# Z7_FUNCTION3.net
KiCad netlist of a schematic drawn in Altium Designer
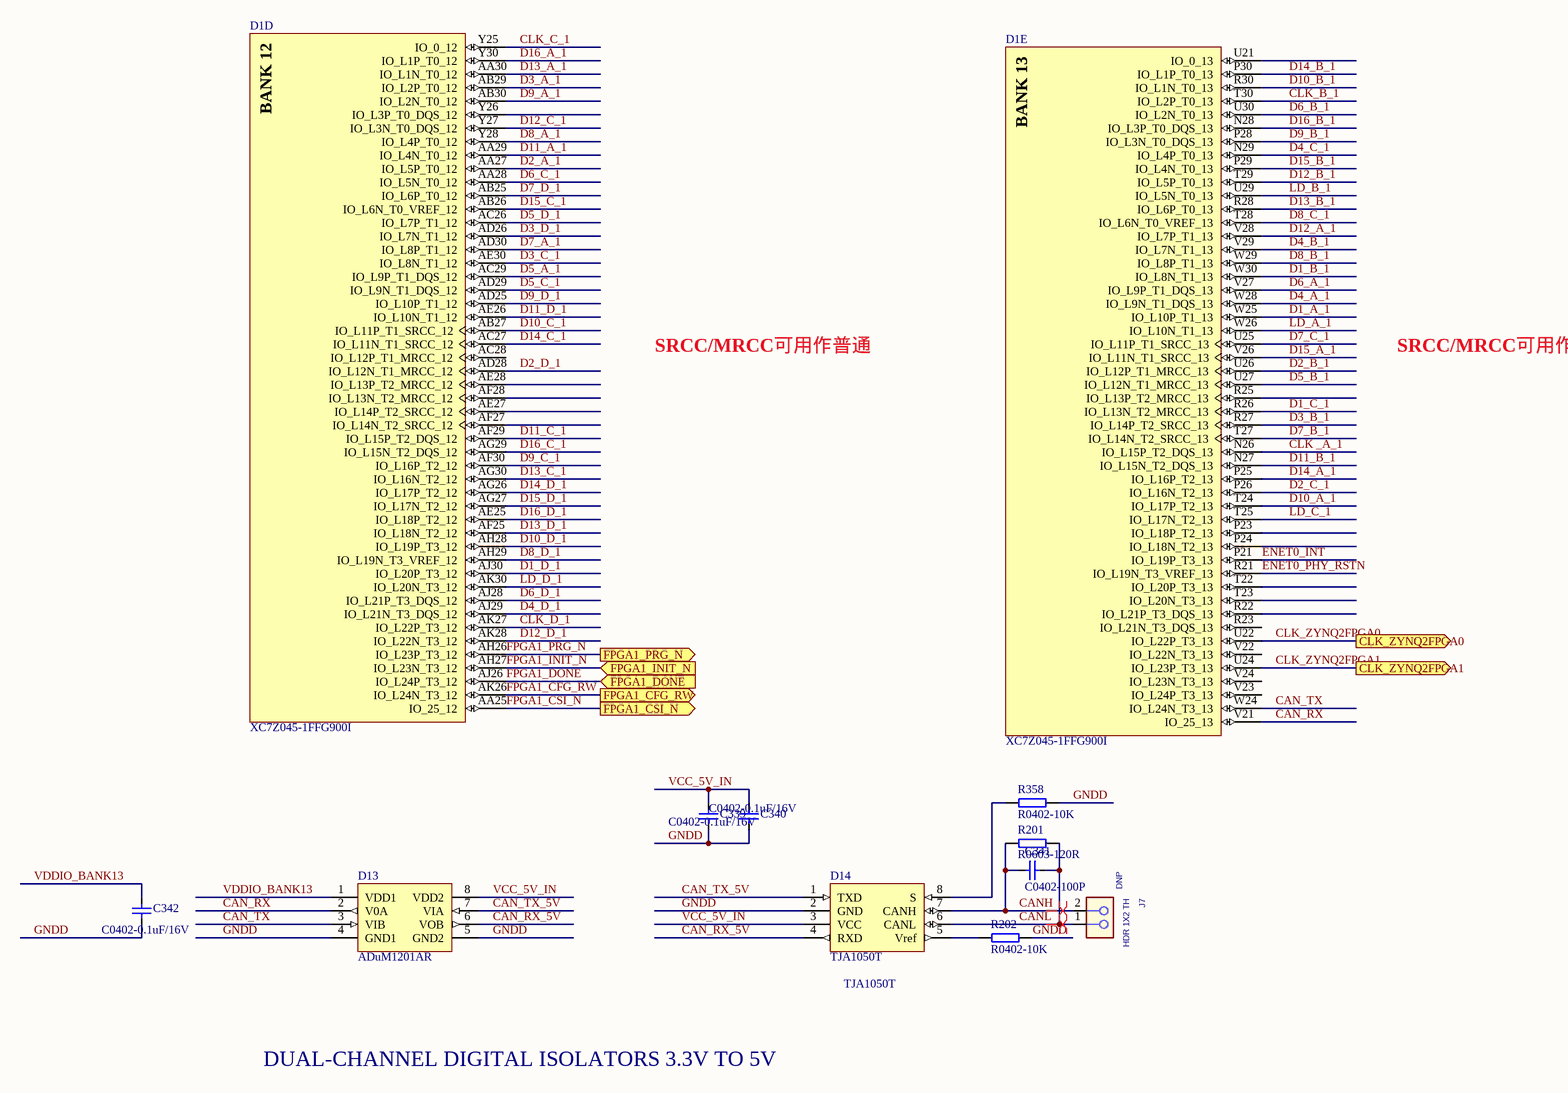
[diagram p0: Z7_FUNCTION3.SchDoc]

(export (version "E")
  (design (tool "Eeschema 10.0.6"))
  (components
    (comp (ref "C339")
      (value "C0402-0.1uF/16V")
      (footprint "C0402")
      (description "X7R")
      (fields (field (name "SCHEMATIC_PART") "CAP") (field (name "MANUFACTURER") "SAMSUNG"))
      (libsource (lib "Database_Libs1") (part "CAP"))
    )
    (comp (ref "C340")
      (value "C0402-0.1uF/16V")
      (footprint "C0402")
      (description "X7R")
      (fields (field (name "SCHEMATIC_PART") "CAP") (field (name "MANUFACTURER") "SAMSUNG"))
      (libsource (lib "Database_Libs1") (part "CAP"))
    )
    (comp (ref "C341")
      (value "C0402-100P")
      (footprint "C0402")
      (description "X7R")
      (fields (field (name "SCHEMATIC_PART") "CAP") (field (name "MANUFACTURER") "SAMSUNG"))
      (libsource (lib "Database_Libs1") (part "CAP"))
    )
    (comp (ref "C342")
      (value "C0402-0.1uF/16V")
      (footprint "C0402")
      (description "X7R")
      (fields (field (name "SCHEMATIC_PART") "CAP") (field (name "MANUFACTURER") "SAMSUNG"))
      (libsource (lib "Database_Libs1") (part "CAP"))
    )
    (comp (ref "D1")
      (value "XC7Z045-1FFG900I")
      (footprint "FFG900")
      (fields (field (name "GENERIC PART NUMBER") "XC7Z045") (field (name "MANUFACTURER") "Xilinx"))
      (libsource (lib "Xilinx Zynq-7000") (part "XC7Z045-1FFG900I"))
    )
    (comp (ref "D13")
      (value "ADuM1201AR")
      (footprint "SOIC-8")
      (description "Quad-Channel Digital Isolators")
      (libsource (lib "Database_Libs1") (part "ADuM1201AR"))
    )
    (comp (ref "D14")
      (value "TJA1050T")
      (footprint "SOIC-8")
      (description "以太网芯片，high speed CAN transceiver,3.3V,SO-8PIN")
      (fields
        (field (name "PART_NUMBER") "TJA1050T")
        (field (name "SCHEMATIC_PART") "TJA1050")
        (field (name "MANUFACTURER") "PHILIPS")
      )
      (libsource (lib "Database_Libs1") (part "TJA1050"))
    )
    (comp (ref "J7")
      (value "HDR 1X2 TH")
      (description "HDR 1X2 TH 100MIL SP 339H AU 98L")
      (fields (field (name "ASSY_OPT") "DNP"))
      (libsource (lib "*") (part "CONN_HDR_2X1"))
    )
    (comp (ref "R201")
      (value "R0603-120R")
      (footprint "R0603")
      (fields (field (name "SCHEMATIC_PART") "RES") (field (name "MANUFACTURER") "YAGEO"))
      (libsource (lib "Database_Libs1") (part "RES"))
    )
    (comp (ref "R202")
      (value "R0402-10K")
      (footprint "R0402")
      (fields (field (name "SCHEMATIC_PART") "RES") (field (name "MANUFACTURER") "SAMSUNG"))
      (libsource (lib "Database_Libs1") (part "RES"))
    )
    (comp (ref "R358")
      (value "R0402-10K")
      (footprint "R0402")
      (fields (field (name "SCHEMATIC_PART") "RES") (field (name "MANUFACTURER") "SAMSUNG"))
      (libsource (lib "Database_Libs1") (part "RES"))
    )
  )
  (nets
    (net (code "1") (name "/CANH") (class "Default")
      (node (ref "C341") (pin "1") (pinfunction "1_1") (pintype "passive"))
      (node (ref "D14") (pin "7") (pinfunction "CANH_7") (pintype "bidirectional"))
      (node (ref "J7") (pin "2") (pinfunction "2_2") (pintype "passive"))
      (node (ref "R201") (pin "2") (pintype "passive"))
    )
    (net (code "2") (name "/CANL") (class "Default")
      (node (ref "C341") (pin "2") (pinfunction "2_2") (pintype "passive"))
      (node (ref "D14") (pin "6") (pinfunction "CANL_6") (pintype "bidirectional"))
      (node (ref "J7") (pin "1") (pinfunction "1_1") (pintype "passive"))
      (node (ref "R201") (pin "1") (pintype "passive"))
    )
    (net (code "3") (name "/CAN_RX") (class "Default")
      (node (ref "D1") (pin "V21") (pinfunction "IO_25_13_V21") (pintype "bidirectional"))
      (node (ref "D13") (pin "2") (pinfunction "V0A_2") (pintype "output"))
    )
    (net (code "4") (name "/CAN_RX_5V") (class "Default")
      (node (ref "D13") (pin "6") (pinfunction "VOB_6") (pintype "output"))
      (node (ref "D14") (pin "4") (pinfunction "RXD_4") (pintype "output"))
    )
    (net (code "5") (name "/CAN_TX") (class "Default")
      (node (ref "D1") (pin "W24") (pinfunction "IO_L24N_T3_13_W24") (pintype "bidirectional"))
      (node (ref "D13") (pin "3") (pinfunction "VIB_3") (pintype "input"))
    )
    (net (code "6") (name "/CAN_TX_5V") (class "Default")
      (node (ref "D13") (pin "7") (pinfunction "VIA_7") (pintype "input"))
      (node (ref "D14") (pin "1") (pinfunction "TXD_1") (pintype "input"))
    )
    (net (code "7") (name "/CLK _A_1") (class "Default")
      (node (ref "D1") (pin "N26") (pinfunction "IO_L15P_T2_DQS_13_N26") (pintype "bidirectional"))
    )
    (net (code "8") (name "/CLK_B_1") (class "Default")
      (node (ref "D1") (pin "T30") (pinfunction "IO_L2P_T0_13_T30") (pintype "bidirectional"))
    )
    (net (code "9") (name "/CLK_C_1") (class "Default")
      (node (ref "D1") (pin "Y25") (pinfunction "IO_0_12_Y25") (pintype "bidirectional"))
    )
    (net (code "10") (name "/CLK_D_1") (class "Default")
      (node (ref "D1") (pin "AK27") (pinfunction "IO_L22P_T3_12_AK27") (pintype "bidirectional"))
    )
    (net (code "11") (name "/CLK_ZYNQ2FPGA0") (class "Default")
      (node (ref "D1") (pin "U22") (pinfunction "IO_L22P_T3_13_U22") (pintype "bidirectional"))
    )
    (net (code "12") (name "/CLK_ZYNQ2FPGA1") (class "Default")
      (node (ref "D1") (pin "U24") (pinfunction "IO_L23P_T3_13_U24") (pintype "bidirectional"))
    )
    (net (code "13") (name "/D1_A_1") (class "Default")
      (node (ref "D1") (pin "W25") (pinfunction "IO_L10P_T1_13_W25") (pintype "bidirectional"))
    )
    (net (code "14") (name "/D1_B_1") (class "Default")
      (node (ref "D1") (pin "W30") (pinfunction "IO_L8N_T1_13_W30") (pintype "bidirectional"))
    )
    (net (code "15") (name "/D1_C_1") (class "Default")
      (node (ref "D1") (pin "R26") (pinfunction "IO_L13N_T2_MRCC_13_R26") (pintype "bidirectional"))
    )
    (net (code "16") (name "/D1_D_1") (class "Default")
      (node (ref "D1") (pin "AJ30") (pinfunction "IO_L20P_T3_12_AJ30") (pintype "bidirectional"))
    )
    (net (code "17") (name "/D2_A_1") (class "Default")
      (node (ref "D1") (pin "AA27") (pinfunction "IO_L5P_T0_12_AA27") (pintype "bidirectional"))
    )
    (net (code "18") (name "/D2_B_1") (class "Default")
      (node (ref "D1") (pin "U26") (pinfunction "IO_L12P_T1_MRCC_13_U26") (pintype "bidirectional"))
    )
    (net (code "19") (name "/D2_C_1") (class "Default")
      (node (ref "D1") (pin "P26") (pinfunction "IO_L16N_T2_13_P26") (pintype "bidirectional"))
    )
    (net (code "20") (name "/D2_D_1") (class "Default")
      (node (ref "D1") (pin "AD28") (pinfunction "IO_L12N_T1_MRCC_12_AD28") (pintype "bidirectional"))
    )
    (net (code "21") (name "/D3_A_1") (class "Default")
      (node (ref "D1") (pin "AB29") (pinfunction "IO_L2P_T0_12_AB29") (pintype "bidirectional"))
    )
    (net (code "22") (name "/D3_B_1") (class "Default")
      (node (ref "D1") (pin "R27") (pinfunction "IO_L14P_T2_SRCC_13_R27") (pintype "bidirectional"))
    )
    (net (code "23") (name "/D3_C_1") (class "Default")
      (node (ref "D1") (pin "AE30") (pinfunction "IO_L8N_T1_12_AE30") (pintype "bidirectional"))
    )
    (net (code "24") (name "/D3_D_1") (class "Default")
      (node (ref "D1") (pin "AD26") (pinfunction "IO_L7N_T1_12_AD26") (pintype "bidirectional"))
    )
    (net (code "25") (name "/D4_A_1") (class "Default")
      (node (ref "D1") (pin "W28") (pinfunction "IO_L9N_T1_DQS_13_W28") (pintype "bidirectional"))
    )
    (net (code "26") (name "/D4_B_1") (class "Default")
      (node (ref "D1") (pin "V29") (pinfunction "IO_L7N_T1_13_V29") (pintype "bidirectional"))
    )
    (net (code "27") (name "/D4_C_1") (class "Default")
      (node (ref "D1") (pin "N29") (pinfunction "IO_L4P_T0_13_N29") (pintype "bidirectional"))
    )
    (net (code "28") (name "/D4_D_1") (class "Default")
      (node (ref "D1") (pin "AJ29") (pinfunction "IO_L21N_T3_DQS_12_AJ29") (pintype "bidirectional"))
    )
    (net (code "29") (name "/D5_A_1") (class "Default")
      (node (ref "D1") (pin "AC29") (pinfunction "IO_L9P_T1_DQS_12_AC29") (pintype "bidirectional"))
    )
    (net (code "30") (name "/D5_B_1") (class "Default")
      (node (ref "D1") (pin "U27") (pinfunction "IO_L12N_T1_MRCC_13_U27") (pintype "bidirectional"))
    )
    (net (code "31") (name "/D5_C_1") (class "Default")
      (node (ref "D1") (pin "AD29") (pinfunction "IO_L9N_T1_DQS_12_AD29") (pintype "bidirectional"))
    )
    (net (code "32") (name "/D5_D_1") (class "Default")
      (node (ref "D1") (pin "AC26") (pinfunction "IO_L7P_T1_12_AC26") (pintype "bidirectional"))
    )
    (net (code "33") (name "/D6_A_1") (class "Default")
      (node (ref "D1") (pin "V27") (pinfunction "IO_L9P_T1_DQS_13_V27") (pintype "bidirectional"))
    )
    (net (code "34") (name "/D6_B_1") (class "Default")
      (node (ref "D1") (pin "U30") (pinfunction "IO_L2N_T0_13_U30") (pintype "bidirectional"))
    )
    (net (code "35") (name "/D6_C_1") (class "Default")
      (node (ref "D1") (pin "AA28") (pinfunction "IO_L5N_T0_12_AA28") (pintype "bidirectional"))
    )
    (net (code "36") (name "/D6_D_1") (class "Default")
      (node (ref "D1") (pin "AJ28") (pinfunction "IO_L21P_T3_DQS_12_AJ28") (pintype "bidirectional"))
    )
    (net (code "37") (name "/D7_A_1") (class "Default")
      (node (ref "D1") (pin "AD30") (pinfunction "IO_L8P_T1_12_AD30") (pintype "bidirectional"))
    )
    (net (code "38") (name "/D7_B_1") (class "Default")
      (node (ref "D1") (pin "T27") (pinfunction "IO_L14N_T2_SRCC_13_T27") (pintype "bidirectional"))
    )
    (net (code "39") (name "/D7_C_1") (class "Default")
      (node (ref "D1") (pin "U25") (pinfunction "IO_L11P_T1_SRCC_13_U25") (pintype "bidirectional"))
    )
    (net (code "40") (name "/D7_D_1") (class "Default")
      (node (ref "D1") (pin "AB25") (pinfunction "IO_L6P_T0_12_AB25") (pintype "bidirectional"))
    )
    (net (code "41") (name "/D8_A_1") (class "Default")
      (node (ref "D1") (pin "Y28") (pinfunction "IO_L4P_T0_12_Y28") (pintype "bidirectional"))
    )
    (net (code "42") (name "/D8_B_1") (class "Default")
      (node (ref "D1") (pin "W29") (pinfunction "IO_L8P_T1_13_W29") (pintype "bidirectional"))
    )
    (net (code "43") (name "/D8_C_1") (class "Default")
      (node (ref "D1") (pin "T28") (pinfunction "IO_L6N_T0_VREF_13_T28") (pintype "bidirectional"))
    )
    (net (code "44") (name "/D8_D_1") (class "Default")
      (node (ref "D1") (pin "AH29") (pinfunction "IO_L19N_T3_VREF_12_AH29") (pintype "bidirectional"))
    )
    (net (code "45") (name "/D9_A_1") (class "Default")
      (node (ref "D1") (pin "AB30") (pinfunction "IO_L2N_T0_12_AB30") (pintype "bidirectional"))
    )
    (net (code "46") (name "/D9_B_1") (class "Default")
      (node (ref "D1") (pin "P28") (pinfunction "IO_L3N_T0_DQS_13_P28") (pintype "bidirectional"))
    )
    (net (code "47") (name "/D9_C_1") (class "Default")
      (node (ref "D1") (pin "AF30") (pinfunction "IO_L16P_T2_12_AF30") (pintype "bidirectional"))
    )
    (net (code "48") (name "/D9_D_1") (class "Default")
      (node (ref "D1") (pin "AD25") (pinfunction "IO_L10P_T1_12_AD25") (pintype "bidirectional"))
    )
    (net (code "49") (name "/D10_A_1") (class "Default")
      (node (ref "D1") (pin "T24") (pinfunction "IO_L17P_T2_13_T24") (pintype "bidirectional"))
    )
    (net (code "50") (name "/D10_B_1") (class "Default")
      (node (ref "D1") (pin "R30") (pinfunction "IO_L1N_T0_13_R30") (pintype "bidirectional"))
    )
    (net (code "51") (name "/D10_C_1") (class "Default")
      (node (ref "D1") (pin "AB27") (pinfunction "IO_L11P_T1_SRCC_12_AB27") (pintype "bidirectional"))
    )
    (net (code "52") (name "/D10_D_1") (class "Default")
      (node (ref "D1") (pin "AH28") (pinfunction "IO_L19P_T3_12_AH28") (pintype "bidirectional"))
    )
    (net (code "53") (name "/D11_A_1") (class "Default")
      (node (ref "D1") (pin "AA29") (pinfunction "IO_L4N_T0_12_AA29") (pintype "bidirectional"))
    )
    (net (code "54") (name "/D11_B_1") (class "Default")
      (node (ref "D1") (pin "N27") (pinfunction "IO_L15N_T2_DQS_13_N27") (pintype "bidirectional"))
    )
    (net (code "55") (name "/D11_C_1") (class "Default")
      (node (ref "D1") (pin "AF29") (pinfunction "IO_L15P_T2_DQS_12_AF29") (pintype "bidirectional"))
    )
    (net (code "56") (name "/D11_D_1") (class "Default")
      (node (ref "D1") (pin "AE26") (pinfunction "IO_L10N_T1_12_AE26") (pintype "bidirectional"))
    )
    (net (code "57") (name "/D12_A_1") (class "Default")
      (node (ref "D1") (pin "V28") (pinfunction "IO_L7P_T1_13_V28") (pintype "bidirectional"))
    )
    (net (code "58") (name "/D12_B_1") (class "Default")
      (node (ref "D1") (pin "T29") (pinfunction "IO_L5P_T0_13_T29") (pintype "bidirectional"))
    )
    (net (code "59") (name "/D12_C_1") (class "Default")
      (node (ref "D1") (pin "Y27") (pinfunction "IO_L3N_T0_DQS_12_Y27") (pintype "bidirectional"))
    )
    (net (code "60") (name "/D12_D_1") (class "Default")
      (node (ref "D1") (pin "AK28") (pinfunction "IO_L22N_T3_12_AK28") (pintype "bidirectional"))
    )
    (net (code "61") (name "/D13_A_1") (class "Default")
      (node (ref "D1") (pin "AA30") (pinfunction "IO_L1N_T0_12_AA30") (pintype "bidirectional"))
    )
    (net (code "62") (name "/D13_B_1") (class "Default")
      (node (ref "D1") (pin "R28") (pinfunction "IO_L6P_T0_13_R28") (pintype "bidirectional"))
    )
    (net (code "63") (name "/D13_C_1") (class "Default")
      (node (ref "D1") (pin "AG30") (pinfunction "IO_L16N_T2_12_AG30") (pintype "bidirectional"))
    )
    (net (code "64") (name "/D13_D_1") (class "Default")
      (node (ref "D1") (pin "AF25") (pinfunction "IO_L18N_T2_12_AF25") (pintype "bidirectional"))
    )
    (net (code "65") (name "/D14_A_1") (class "Default")
      (node (ref "D1") (pin "P25") (pinfunction "IO_L16P_T2_13_P25") (pintype "bidirectional"))
    )
    (net (code "66") (name "/D14_B_1") (class "Default")
      (node (ref "D1") (pin "P30") (pinfunction "IO_L1P_T0_13_P30") (pintype "bidirectional"))
    )
    (net (code "67") (name "/D14_C_1") (class "Default")
      (node (ref "D1") (pin "AC27") (pinfunction "IO_L11N_T1_SRCC_12_AC27") (pintype "bidirectional"))
    )
    (net (code "68") (name "/D14_D_1") (class "Default")
      (node (ref "D1") (pin "AG26") (pinfunction "IO_L17P_T2_12_AG26") (pintype "bidirectional"))
    )
    (net (code "69") (name "/D15_A_1") (class "Default")
      (node (ref "D1") (pin "V26") (pinfunction "IO_L11N_T1_SRCC_13_V26") (pintype "bidirectional"))
    )
    (net (code "70") (name "/D15_B_1") (class "Default")
      (node (ref "D1") (pin "P29") (pinfunction "IO_L4N_T0_13_P29") (pintype "bidirectional"))
    )
    (net (code "71") (name "/D15_C_1") (class "Default")
      (node (ref "D1") (pin "AB26") (pinfunction "IO_L6N_T0_VREF_12_AB26") (pintype "bidirectional"))
    )
    (net (code "72") (name "/D15_D_1") (class "Default")
      (node (ref "D1") (pin "AG27") (pinfunction "IO_L17N_T2_12_AG27") (pintype "bidirectional"))
    )
    (net (code "73") (name "/D16_A_1") (class "Default")
      (node (ref "D1") (pin "Y30") (pinfunction "IO_L1P_T0_12_Y30") (pintype "bidirectional"))
    )
    (net (code "74") (name "/D16_B_1") (class "Default")
      (node (ref "D1") (pin "N28") (pinfunction "IO_L3P_T0_DQS_13_N28") (pintype "bidirectional"))
    )
    (net (code "75") (name "/D16_C_1") (class "Default")
      (node (ref "D1") (pin "AG29") (pinfunction "IO_L15N_T2_DQS_12_AG29") (pintype "bidirectional"))
    )
    (net (code "76") (name "/D16_D_1") (class "Default")
      (node (ref "D1") (pin "AE25") (pinfunction "IO_L18P_T2_12_AE25") (pintype "bidirectional"))
    )
    (net (code "77") (name "/ENET0_INT") (class "Default")
      (node (ref "D1") (pin "P21") (pinfunction "IO_L19P_T3_13_P21") (pintype "bidirectional"))
    )
    (net (code "78") (name "/ENET0_PHY_RSTN") (class "Default")
      (node (ref "D1") (pin "R21") (pinfunction "IO_L19N_T3_VREF_13_R21") (pintype "bidirectional"))
    )
    (net (code "79") (name "/FPGA1_CFG_RW") (class "Default")
      (node (ref "D1") (pin "AK26") (pinfunction "IO_L24N_T3_12_AK26") (pintype "bidirectional"))
    )
    (net (code "80") (name "/FPGA1_CSI_N") (class "Default")
      (node (ref "D1") (pin "AA25") (pinfunction "IO_25_12_AA25") (pintype "bidirectional"))
    )
    (net (code "81") (name "/FPGA1_DONE") (class "Default")
      (node (ref "D1") (pin "AJ26") (pinfunction "IO_L24P_T3_12_AJ26") (pintype "bidirectional"))
    )
    (net (code "82") (name "/FPGA1_INIT_N") (class "Default")
      (node (ref "D1") (pin "AH27") (pinfunction "IO_L23N_T3_12_AH27") (pintype "bidirectional"))
    )
    (net (code "83") (name "/FPGA1_PRG_N") (class "Default")
      (node (ref "D1") (pin "AH26") (pinfunction "IO_L23P_T3_12_AH26") (pintype "bidirectional"))
    )
    (net (code "84") (name "/GNDD") (class "Default")
      (node (ref "C339") (pin "1") (pinfunction "1_1") (pintype "passive"))
      (node (ref "C340") (pin "1") (pinfunction "1_1") (pintype "passive"))
      (node (ref "C342") (pin "1") (pinfunction "1_1") (pintype "passive"))
      (node (ref "D13") (pin "4") (pinfunction "GND1_4") (pintype "power_in"))
      (node (ref "D13") (pin "5") (pinfunction "GND2_5") (pintype "power_in"))
      (node (ref "D14") (pin "2") (pinfunction "GND_2") (pintype "power_in"))
      (node (ref "R202") (pin "2") (pintype "passive"))
      (node (ref "R358") (pin "2") (pintype "passive"))
    )
    (net (code "85") (name "/LD_A_1") (class "Default")
      (node (ref "D1") (pin "W26") (pinfunction "IO_L10N_T1_13_W26") (pintype "bidirectional"))
    )
    (net (code "86") (name "/LD_B_1") (class "Default")
      (node (ref "D1") (pin "U29") (pinfunction "IO_L5N_T0_13_U29") (pintype "bidirectional"))
    )
    (net (code "87") (name "/LD_C_1") (class "Default")
      (node (ref "D1") (pin "T25") (pinfunction "IO_L17N_T2_13_T25") (pintype "bidirectional"))
    )
    (net (code "88") (name "/LD_D_1") (class "Default")
      (node (ref "D1") (pin "AK30") (pinfunction "IO_L20N_T3_12_AK30") (pintype "bidirectional"))
    )
    (net (code "89") (name "/VCC_5V_IN") (class "Default")
      (node (ref "C339") (pin "2") (pinfunction "2_2") (pintype "passive"))
      (node (ref "C340") (pin "2") (pinfunction "2_2") (pintype "passive"))
      (node (ref "D13") (pin "8") (pinfunction "VDD2_8") (pintype "power_in"))
      (node (ref "D14") (pin "3") (pinfunction "VCC_3") (pintype "power_in"))
    )
    (net (code "90") (name "/VDDIO_BANK13") (class "Default")
      (node (ref "C342") (pin "2") (pinfunction "2_2") (pintype "passive"))
      (node (ref "D13") (pin "1") (pinfunction "VDD1_1") (pintype "power_in"))
    )
    (net (code "91") (name "Net-(D14-S)") (class "Default")
      (node (ref "D14") (pin "8") (pinfunction "S_8") (pintype "input"))
      (node (ref "R358") (pin "1") (pintype "passive"))
    )
    (net (code "92") (name "Net-(D14-Vref)") (class "Default")
      (node (ref "D14") (pin "5") (pinfunction "Vref_5") (pintype "output"))
      (node (ref "R202") (pin "1") (pintype "passive"))
    )
    (net (code "93") (name "unconnected-(D1D-IO_L3P_T0_DQS_12-PadY26)") (class "Default")
      (node (ref "D1") (pin "Y26") (pinfunction "IO_L3P_T0_DQS_12_Y26") (pintype "bidirectional"))
    )
    (net (code "94") (name "unconnected-(D1D-IO_L12P_T1_MRCC_12-PadAC28)") (class "Default")
      (node (ref "D1") (pin "AC28") (pinfunction "IO_L12P_T1_MRCC_12_AC28") (pintype "bidirectional"))
    )
    (net (code "95") (name "unconnected-(D1D-IO_L13N_T2_MRCC_12-PadAF28)") (class "Default")
      (node (ref "D1") (pin "AF28") (pinfunction "IO_L13N_T2_MRCC_12_AF28") (pintype "bidirectional"))
    )
    (net (code "96") (name "unconnected-(D1D-IO_L13P_T2_MRCC_12-PadAE28)") (class "Default")
      (node (ref "D1") (pin "AE28") (pinfunction "IO_L13P_T2_MRCC_12_AE28") (pintype "bidirectional"))
    )
    (net (code "97") (name "unconnected-(D1D-IO_L14N_T2_SRCC_12-PadAF27)") (class "Default")
      (node (ref "D1") (pin "AF27") (pinfunction "IO_L14N_T2_SRCC_12_AF27") (pintype "bidirectional"))
    )
    (net (code "98") (name "unconnected-(D1D-IO_L14P_T2_SRCC_12-PadAE27)") (class "Default")
      (node (ref "D1") (pin "AE27") (pinfunction "IO_L14P_T2_SRCC_12_AE27") (pintype "bidirectional"))
    )
    (net (code "99") (name "unconnected-(D1E-IO_0_13-PadU21)") (class "Default")
      (node (ref "D1") (pin "U21") (pinfunction "IO_0_13_U21") (pintype "bidirectional"))
    )
    (net (code "100") (name "unconnected-(D1E-IO_L13P_T2_MRCC_13-PadR25)") (class "Default")
      (node (ref "D1") (pin "R25") (pinfunction "IO_L13P_T2_MRCC_13_R25") (pintype "bidirectional"))
    )
    (net (code "101") (name "unconnected-(D1E-IO_L18N_T2_13-PadP24)") (class "Default")
      (node (ref "D1") (pin "P24") (pinfunction "IO_L18N_T2_13_P24") (pintype "bidirectional"))
    )
    (net (code "102") (name "unconnected-(D1E-IO_L18P_T2_13-PadP23)") (class "Default")
      (node (ref "D1") (pin "P23") (pinfunction "IO_L18P_T2_13_P23") (pintype "bidirectional"))
    )
    (net (code "103") (name "unconnected-(D1E-IO_L20N_T3_13-PadT23)") (class "Default")
      (node (ref "D1") (pin "T23") (pinfunction "IO_L20N_T3_13_T23") (pintype "bidirectional"))
    )
    (net (code "104") (name "unconnected-(D1E-IO_L20P_T3_13-PadT22)") (class "Default")
      (node (ref "D1") (pin "T22") (pinfunction "IO_L20P_T3_13_T22") (pintype "bidirectional"))
    )
    (net (code "105") (name "unconnected-(D1E-IO_L21N_T3_DQS_13-PadR23)") (class "Default")
      (node (ref "D1") (pin "R23") (pinfunction "IO_L21N_T3_DQS_13_R23") (pintype "bidirectional"))
    )
    (net (code "106") (name "unconnected-(D1E-IO_L21P_T3_DQS_13-PadR22)") (class "Default")
      (node (ref "D1") (pin "R22") (pinfunction "IO_L21P_T3_DQS_13_R22") (pintype "bidirectional"))
    )
    (net (code "107") (name "unconnected-(D1E-IO_L22N_T3_13-PadV22)") (class "Default")
      (node (ref "D1") (pin "V22") (pinfunction "IO_L22N_T3_13_V22") (pintype "bidirectional"))
    )
    (net (code "108") (name "unconnected-(D1E-IO_L23N_T3_13-PadV24)") (class "Default")
      (node (ref "D1") (pin "V24") (pinfunction "IO_L23N_T3_13_V24") (pintype "bidirectional"))
    )
    (net (code "109") (name "unconnected-(D1E-IO_L24P_T3_13-PadV23)") (class "Default")
      (node (ref "D1") (pin "V23") (pinfunction "IO_L24P_T3_13_V23") (pintype "bidirectional"))
    )
  )
)
